# SCH_robotica_2023-06-20.net
KiCad netlist of a schematic drawn in EasyEDA
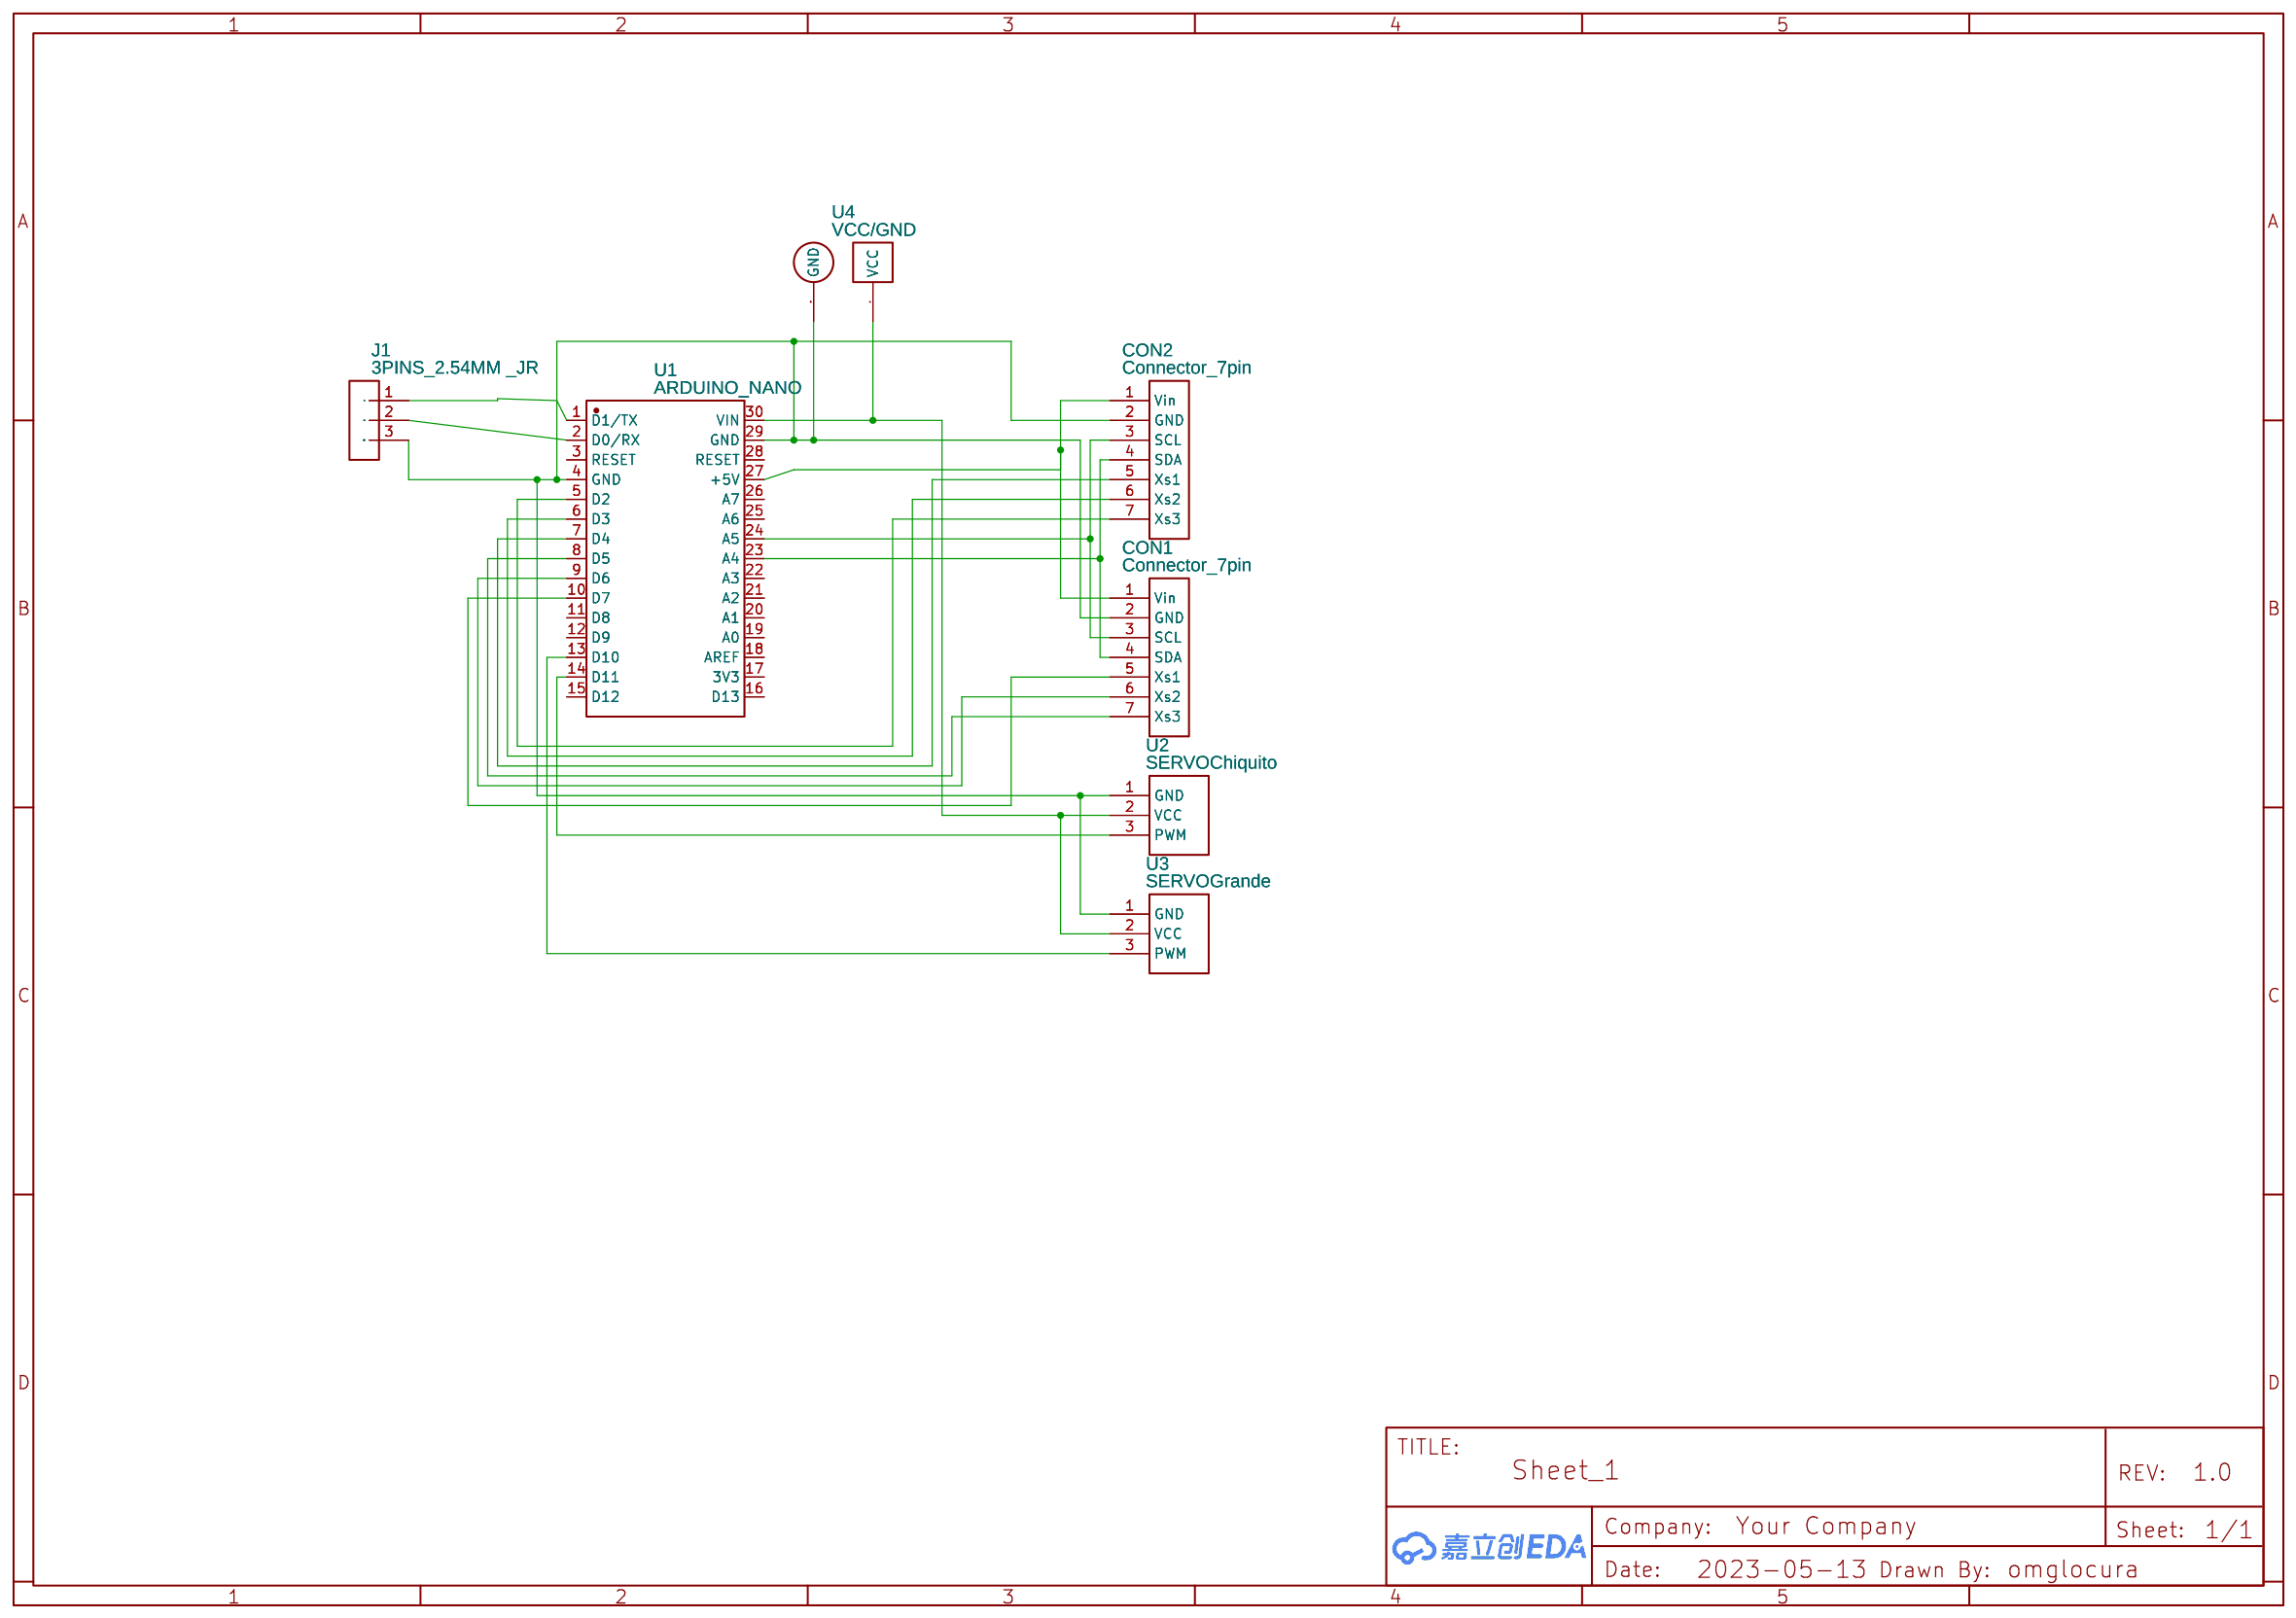
[diagram p0: schematic sheet]

(export (version "E")
  (design (tool "Eeschema 10.0.6"))
  (components
    (comp (ref "CON1") (value "Connector_7pin") (libsource (lib "") (part "Connector_7pin")))
    (comp (ref "CON2") (value "Connector_7pin") (libsource (lib "") (part "Connector_7pin")))
    (comp (ref "J1")
      (value "3PINS_2.54MM _JR")
      (fields (field (name "BOM_Supplier Part") "undefined"))
      (libsource (lib "") (part "3PINS_2.54MM _JR"))
    )
    (comp (ref "U1")
      (value "ARDUINO_NANO")
      (fields (field (name "BOM_Supplier Part") "C9900017879"))
      (libsource (lib "") (part "ARDUINO_NANO"))
    )
    (comp (ref "U2") (value "SERVOChiquito") (libsource (lib "") (part "SERVOPINS")))
    (comp (ref "U3") (value "SERVOGrande") (libsource (lib "") (part "SERVOPINS")))
    (comp (ref "U4")
      (value "VCC/GND")
      (fields
        (field (name "BOM_Manufacturer Part") "VCC/GND 2PIN")
        (field (name "BOM_Supplier Part") "TUANHUNG")
      )
      (libsource (lib "") (part "VCC/GND"))
    )
  )
  (nets
    (net (code "1") (name "Net-(CON1-GND)") (class "Default")
      (node (ref "CON1") (pin "2") (pinfunction "GND_2") (pintype "unspecified"))
      (node (ref "CON2") (pin "2") (pinfunction "GND_2") (pintype "unspecified"))
      (node (ref "J1") (pin "3") (pinfunction "GND_3") (pintype "unspecified"))
      (node (ref "U1") (pin "29") (pinfunction "GND_29") (pintype "unspecified"))
      (node (ref "U1") (pin "4") (pinfunction "GND_4") (pintype "unspecified"))
      (node (ref "U2") (pin "1") (pinfunction "GND_1") (pintype "unspecified"))
      (node (ref "U3") (pin "1") (pinfunction "GND_1") (pintype "unspecified"))
      (node (ref "U4") (pin "2") (pinfunction "GND_2") (pintype "unspecified"))
    )
    (net (code "2") (name "Net-(CON1-SCL)") (class "Default")
      (node (ref "CON1") (pin "3") (pinfunction "SCL_3") (pintype "unspecified"))
      (node (ref "CON2") (pin "3") (pinfunction "SCL_3") (pintype "unspecified"))
      (node (ref "U1") (pin "24") (pinfunction "A5_24") (pintype "unspecified"))
    )
    (net (code "3") (name "Net-(CON1-SDA)") (class "Default")
      (node (ref "CON1") (pin "4") (pinfunction "SDA_4") (pintype "unspecified"))
      (node (ref "CON2") (pin "4") (pinfunction "SDA_4") (pintype "unspecified"))
      (node (ref "U1") (pin "23") (pinfunction "A4_23") (pintype "unspecified"))
    )
    (net (code "4") (name "Net-(CON1-Vin)") (class "Default")
      (node (ref "CON1") (pin "1") (pinfunction "Vin_1") (pintype "unspecified"))
      (node (ref "CON2") (pin "1") (pinfunction "Vin_1") (pintype "unspecified"))
      (node (ref "U1") (pin "27") (pinfunction "+5V_27") (pintype "unspecified"))
    )
    (net (code "5") (name "Net-(CON1-Xs1)") (class "Default")
      (node (ref "CON1") (pin "5") (pinfunction "Xs1_5") (pintype "unspecified"))
      (node (ref "U1") (pin "10") (pinfunction "D7_10") (pintype "unspecified"))
    )
    (net (code "6") (name "Net-(CON1-Xs2)") (class "Default")
      (node (ref "CON1") (pin "6") (pinfunction "Xs2_6") (pintype "unspecified"))
      (node (ref "U1") (pin "9") (pinfunction "D6_9") (pintype "unspecified"))
    )
    (net (code "7") (name "Net-(CON1-Xs3)") (class "Default")
      (node (ref "CON1") (pin "7") (pinfunction "Xs3_7") (pintype "unspecified"))
      (node (ref "U1") (pin "8") (pinfunction "D5_8") (pintype "unspecified"))
    )
    (net (code "8") (name "Net-(CON2-Xs1)") (class "Default")
      (node (ref "CON2") (pin "5") (pinfunction "Xs1_5") (pintype "unspecified"))
      (node (ref "U1") (pin "7") (pinfunction "D4_7") (pintype "unspecified"))
    )
    (net (code "9") (name "Net-(CON2-Xs2)") (class "Default")
      (node (ref "CON2") (pin "6") (pinfunction "Xs2_6") (pintype "unspecified"))
      (node (ref "U1") (pin "6") (pinfunction "D3_6") (pintype "unspecified"))
    )
    (net (code "10") (name "Net-(CON2-Xs3)") (class "Default")
      (node (ref "CON2") (pin "7") (pinfunction "Xs3_7") (pintype "unspecified"))
      (node (ref "U1") (pin "5") (pinfunction "D2_5") (pintype "unspecified"))
    )
    (net (code "11") (name "Net-(J1-Rx)") (class "Default")
      (node (ref "J1") (pin "2") (pinfunction "Rx_2") (pintype "unspecified"))
      (node (ref "U1") (pin "2") (pinfunction "D0/RX_2") (pintype "unspecified"))
    )
    (net (code "12") (name "Net-(J1-Tx)") (class "Default")
      (node (ref "J1") (pin "1") (pinfunction "Tx_1") (pintype "unspecified"))
      (node (ref "U1") (pin "1") (pinfunction "D1/TX_1") (pintype "unspecified"))
    )
    (net (code "13") (name "Net-(U1-D10)") (class "Default")
      (node (ref "U1") (pin "13") (pinfunction "D10_13") (pintype "unspecified"))
      (node (ref "U3") (pin "3") (pinfunction "PWM_3") (pintype "unspecified"))
    )
    (net (code "14") (name "Net-(U1-D11)") (class "Default")
      (node (ref "U1") (pin "14") (pinfunction "D11_14") (pintype "unspecified"))
      (node (ref "U2") (pin "3") (pinfunction "PWM_3") (pintype "unspecified"))
    )
    (net (code "15") (name "Net-(U1-VIN)") (class "Default")
      (node (ref "U1") (pin "30") (pinfunction "VIN_30") (pintype "unspecified"))
      (node (ref "U2") (pin "2") (pinfunction "VCC_2") (pintype "unspecified"))
      (node (ref "U3") (pin "2") (pinfunction "VCC_2") (pintype "unspecified"))
      (node (ref "U4") (pin "1") (pinfunction "VCC_1") (pintype "unspecified"))
    )
    (net (code "16") (name "unconnected-(U1-3V3-Pad17)") (class "Default")
      (node (ref "U1") (pin "17") (pinfunction "3V3_17") (pintype "unspecified"))
    )
    (net (code "17") (name "unconnected-(U1-A0-Pad19)") (class "Default")
      (node (ref "U1") (pin "19") (pinfunction "A0_19") (pintype "unspecified"))
    )
    (net (code "18") (name "unconnected-(U1-A1-Pad20)") (class "Default")
      (node (ref "U1") (pin "20") (pinfunction "A1_20") (pintype "unspecified"))
    )
    (net (code "19") (name "unconnected-(U1-A2-Pad21)") (class "Default")
      (node (ref "U1") (pin "21") (pinfunction "A2_21") (pintype "unspecified"))
    )
    (net (code "20") (name "unconnected-(U1-A3-Pad22)") (class "Default")
      (node (ref "U1") (pin "22") (pinfunction "A3_22") (pintype "unspecified"))
    )
    (net (code "21") (name "unconnected-(U1-A6-Pad25)") (class "Default")
      (node (ref "U1") (pin "25") (pinfunction "A6_25") (pintype "unspecified"))
    )
    (net (code "22") (name "unconnected-(U1-A7-Pad26)") (class "Default")
      (node (ref "U1") (pin "26") (pinfunction "A7_26") (pintype "unspecified"))
    )
    (net (code "23") (name "unconnected-(U1-AREF-Pad18)") (class "Default")
      (node (ref "U1") (pin "18") (pinfunction "AREF_18") (pintype "unspecified"))
    )
    (net (code "24") (name "unconnected-(U1-D8-Pad11)") (class "Default")
      (node (ref "U1") (pin "11") (pinfunction "D8_11") (pintype "unspecified"))
    )
    (net (code "25") (name "unconnected-(U1-D9-Pad12)") (class "Default")
      (node (ref "U1") (pin "12") (pinfunction "D9_12") (pintype "unspecified"))
    )
    (net (code "26") (name "unconnected-(U1-D12-Pad15)") (class "Default")
      (node (ref "U1") (pin "15") (pinfunction "D12_15") (pintype "unspecified"))
    )
    (net (code "27") (name "unconnected-(U1-D13-Pad16)") (class "Default")
      (node (ref "U1") (pin "16") (pinfunction "D13_16") (pintype "unspecified"))
    )
    (net (code "28") (name "unconnected-(U1-RESET-Pad3)") (class "Default")
      (node (ref "U1") (pin "3") (pinfunction "RESET_3") (pintype "unspecified"))
    )
    (net (code "29") (name "unconnected-(U1-RESET-Pad28)") (class "Default")
      (node (ref "U1") (pin "28") (pinfunction "RESET_28") (pintype "unspecified"))
    )
  )
)
